# 14_Clocks_2.net
KiCad netlist of a schematic drawn in Altium Designer
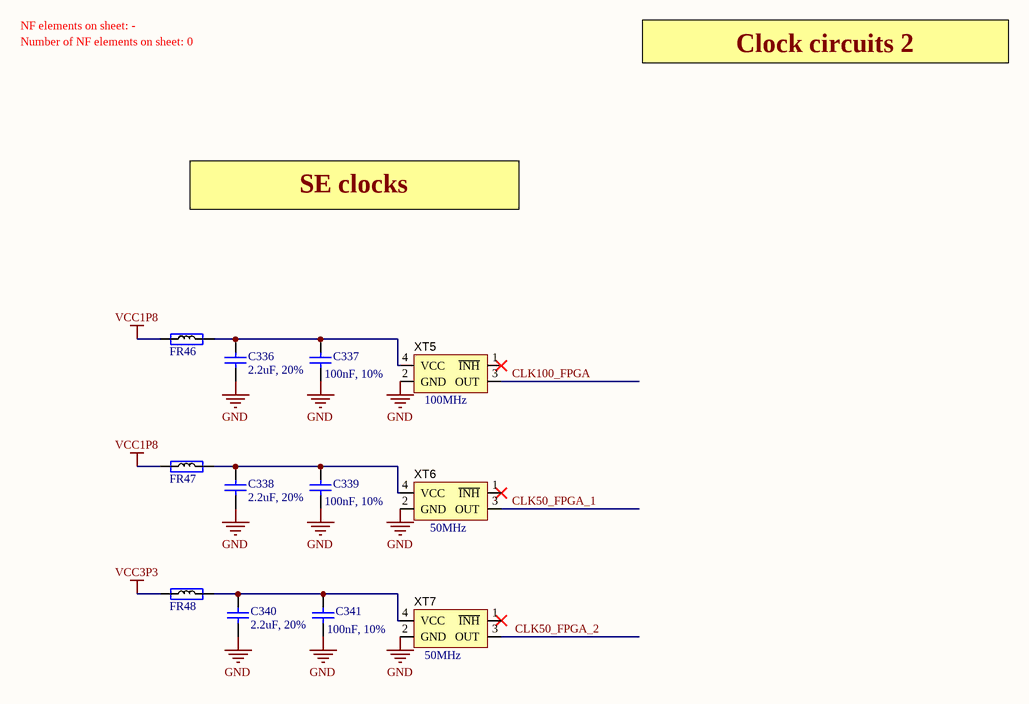
[diagram p0: 14_Clocks_2.SchDoc]

(export (version "E")
  (design (tool "Eeschema 10.0.6"))
  (components
    (comp (ref "C336")
      (value "2.2uF, 20%")
      (footprint "LimeMicroAltiumLib_pcbLib:CAP0402")
      (fields (field (name "MANUFACTURER") "TDK Corporation") (field (name "TOLERANCE") "±20%"))
      (libsource (lib "LimeMicroAltiumLib_schLib") (part "Cap_0402"))
    )
    (comp (ref "C337")
      (value "100nF, 10%")
      (footprint "LimeMicroAltiumLib_pcbLib:CAP0402")
      (fields
        (field (name "TOLERANCE") "10 %")
        (field (name "MANUFACTURER") "Murata")
        (field (name "MANUFACTURER PART NUMBER") "GRM155R71C104KA88D")
      )
      (libsource (lib "LimeFPGAboard_schLib") (part "Cap_0603"))
    )
    (comp (ref "C338")
      (value "2.2uF, 20%")
      (footprint "LimeMicroAltiumLib_pcbLib:CAP0402")
      (fields (field (name "MANUFACTURER") "TDK Corporation") (field (name "TOLERANCE") "±20%"))
      (libsource (lib "LimeMicroAltiumLib_schLib") (part "Cap_0402"))
    )
    (comp (ref "C339")
      (value "100nF, 10%")
      (footprint "LimeMicroAltiumLib_pcbLib:CAP0402")
      (fields
        (field (name "TOLERANCE") "10 %")
        (field (name "MANUFACTURER") "Murata")
        (field (name "MANUFACTURER PART NUMBER") "GRM155R71C104KA88D")
      )
      (libsource (lib "LimeFPGAboard_schLib") (part "Cap_0603"))
    )
    (comp (ref "C340")
      (value "2.2uF, 20%")
      (footprint "LimeMicroAltiumLib_pcbLib:CAP0402")
      (fields (field (name "MANUFACTURER") "TDK Corporation") (field (name "TOLERANCE") "±20%"))
      (libsource (lib "LimeMicroAltiumLib_schLib") (part "Cap_0402"))
    )
    (comp (ref "C341")
      (value "100nF, 10%")
      (footprint "LimeMicroAltiumLib_pcbLib:CAP0402")
      (fields
        (field (name "TOLERANCE") "10 %")
        (field (name "MANUFACTURER") "Murata")
        (field (name "MANUFACTURER PART NUMBER") "GRM155R71C104KA88D")
      )
      (libsource (lib "LimeFPGAboard_schLib") (part "Cap_0603"))
    )
    (comp (ref "FR46")
      (value "Ferrite")
      (footprint "LimeMicroAltiumLib_pcbLib:RES0201")
      (fields (field (name "MANUFACTURER") "Taiyo Yuden"))
      (libsource (lib "LimeMicroAltiumLib_schLib") (part "Ferrite"))
    )
    (comp (ref "FR47")
      (value "Ferrite")
      (footprint "LimeMicroAltiumLib_pcbLib:RES0201")
      (fields (field (name "MANUFACTURER") "Taiyo Yuden"))
      (libsource (lib "LimeMicroAltiumLib_schLib") (part "Ferrite"))
    )
    (comp (ref "FR48")
      (value "Ferrite")
      (footprint "LimeMicroAltiumLib_pcbLib:RES0201")
      (fields (field (name "MANUFACTURER") "Taiyo Yuden"))
      (libsource (lib "LimeMicroAltiumLib_schLib") (part "Ferrite"))
    )
    (comp (ref "XT5")
      (value "100MHz")
      (footprint "CRYSTAL_4-LCC_v4")
      (description "Oscillator Crystal")
      (fields
        (field (name "MANUFACTURER PART NUMBER") "KC5032A100.000C1GE00")
        (field (name "MANUFACTURER") "AVX Corp/Kyocera Corp")
      )
      (libsource (lib "LimeMicroAltiumLib_schLib") (part "CRYSTAL"))
    )
    (comp (ref "XT6")
      (value "50MHz")
      (footprint "CRYSTAL_4-LCC_v4")
      (description "Oscillator Crystal")
      (fields
        (field (name "MANUFACTURER PART NUMBER") "KC5032A50.0000CMGE00")
        (field (name "MANUFACTURER") "AVX Corp/Kyocera Corp")
      )
      (libsource (lib "LimeMicroAltiumLib_schLib") (part "CRYSTAL"))
    )
    (comp (ref "XT7")
      (value "50MHz")
      (footprint "CRYSTAL_4-LCC_v4")
      (description "Oscillator Crystal")
      (fields
        (field (name "MANUFACTURER PART NUMBER") "KC5032A50.0000CMGE00")
        (field (name "MANUFACTURER") "AVX Corp/Kyocera Corp")
      )
      (libsource (lib "LimeMicroAltiumLib_schLib") (part "CRYSTAL"))
    )
  )
  (nets
    (net (code "1") (name "/CLK50_FPGA_1") (class "Default")
      (node (ref "XT6") (pin "3") (pinfunction "OUT_3") (pintype "passive"))
    )
    (net (code "2") (name "/CLK50_FPGA_2") (class "Default")
      (node (ref "XT7") (pin "3") (pinfunction "OUT_3") (pintype "passive"))
    )
    (net (code "3") (name "/CLK100_FPGA") (class "Default")
      (node (ref "XT5") (pin "3") (pinfunction "OUT_3") (pintype "passive"))
    )
    (net (code "4") (name "GND") (class "Default")
      (node (ref "C336") (pin "1") (pinfunction "1_1") (pintype "passive"))
      (node (ref "C337") (pin "2") (pinfunction "2_2") (pintype "passive"))
      (node (ref "C338") (pin "1") (pinfunction "1_1") (pintype "passive"))
      (node (ref "C339") (pin "2") (pinfunction "2_2") (pintype "passive"))
      (node (ref "C340") (pin "1") (pinfunction "1_1") (pintype "passive"))
      (node (ref "C341") (pin "2") (pinfunction "2_2") (pintype "passive"))
      (node (ref "XT5") (pin "2") (pinfunction "GND_2") (pintype "passive"))
      (node (ref "XT6") (pin "2") (pinfunction "GND_2") (pintype "passive"))
      (node (ref "XT7") (pin "2") (pinfunction "GND_2") (pintype "passive"))
    )
    (net (code "5") (name "Net-(XT5-VCC)") (class "Default")
      (node (ref "C336") (pin "2") (pinfunction "2_2") (pintype "passive"))
      (node (ref "C337") (pin "1") (pinfunction "1_1") (pintype "passive"))
      (node (ref "FR46") (pin "2") (pinfunction "2_2") (pintype "passive"))
      (node (ref "XT5") (pin "4") (pinfunction "VCC_4") (pintype "passive"))
    )
    (net (code "6") (name "Net-(XT6-VCC)") (class "Default")
      (node (ref "C338") (pin "2") (pinfunction "2_2") (pintype "passive"))
      (node (ref "C339") (pin "1") (pinfunction "1_1") (pintype "passive"))
      (node (ref "FR47") (pin "2") (pinfunction "2_2") (pintype "passive"))
      (node (ref "XT6") (pin "4") (pinfunction "VCC_4") (pintype "passive"))
    )
    (net (code "7") (name "Net-(XT7-VCC)") (class "Default")
      (node (ref "C340") (pin "2") (pinfunction "2_2") (pintype "passive"))
      (node (ref "C341") (pin "1") (pinfunction "1_1") (pintype "passive"))
      (node (ref "FR48") (pin "2") (pinfunction "2_2") (pintype "passive"))
      (node (ref "XT7") (pin "4") (pinfunction "VCC_4") (pintype "passive"))
    )
    (net (code "8") (name "VCC1P8") (class "Default")
      (node (ref "FR46") (pin "1") (pinfunction "1_1") (pintype "passive"))
      (node (ref "FR47") (pin "1") (pinfunction "1_1") (pintype "passive"))
    )
    (net (code "9") (name "VCC3P3") (class "Default")
      (node (ref "FR48") (pin "1") (pinfunction "1_1") (pintype "passive"))
    )
    (net (code "10") (name "unconnected-(XT5-~{INH}-Pad1)") (class "Default")
      (node (ref "XT5") (pin "1") (pinfunction "~{INH}_1") (pintype "passive+no_connect"))
    )
    (net (code "11") (name "unconnected-(XT6-~{INH}-Pad1)") (class "Default")
      (node (ref "XT6") (pin "1") (pinfunction "~{INH}_1") (pintype "passive+no_connect"))
    )
    (net (code "12") (name "unconnected-(XT7-~{INH}-Pad1)") (class "Default")
      (node (ref "XT7") (pin "1") (pinfunction "~{INH}_1") (pintype "passive+no_connect"))
    )
  )
)
